# 2_bootleg-3-matrix.net
KiCad netlist of a schematic drawn in Altium Designer
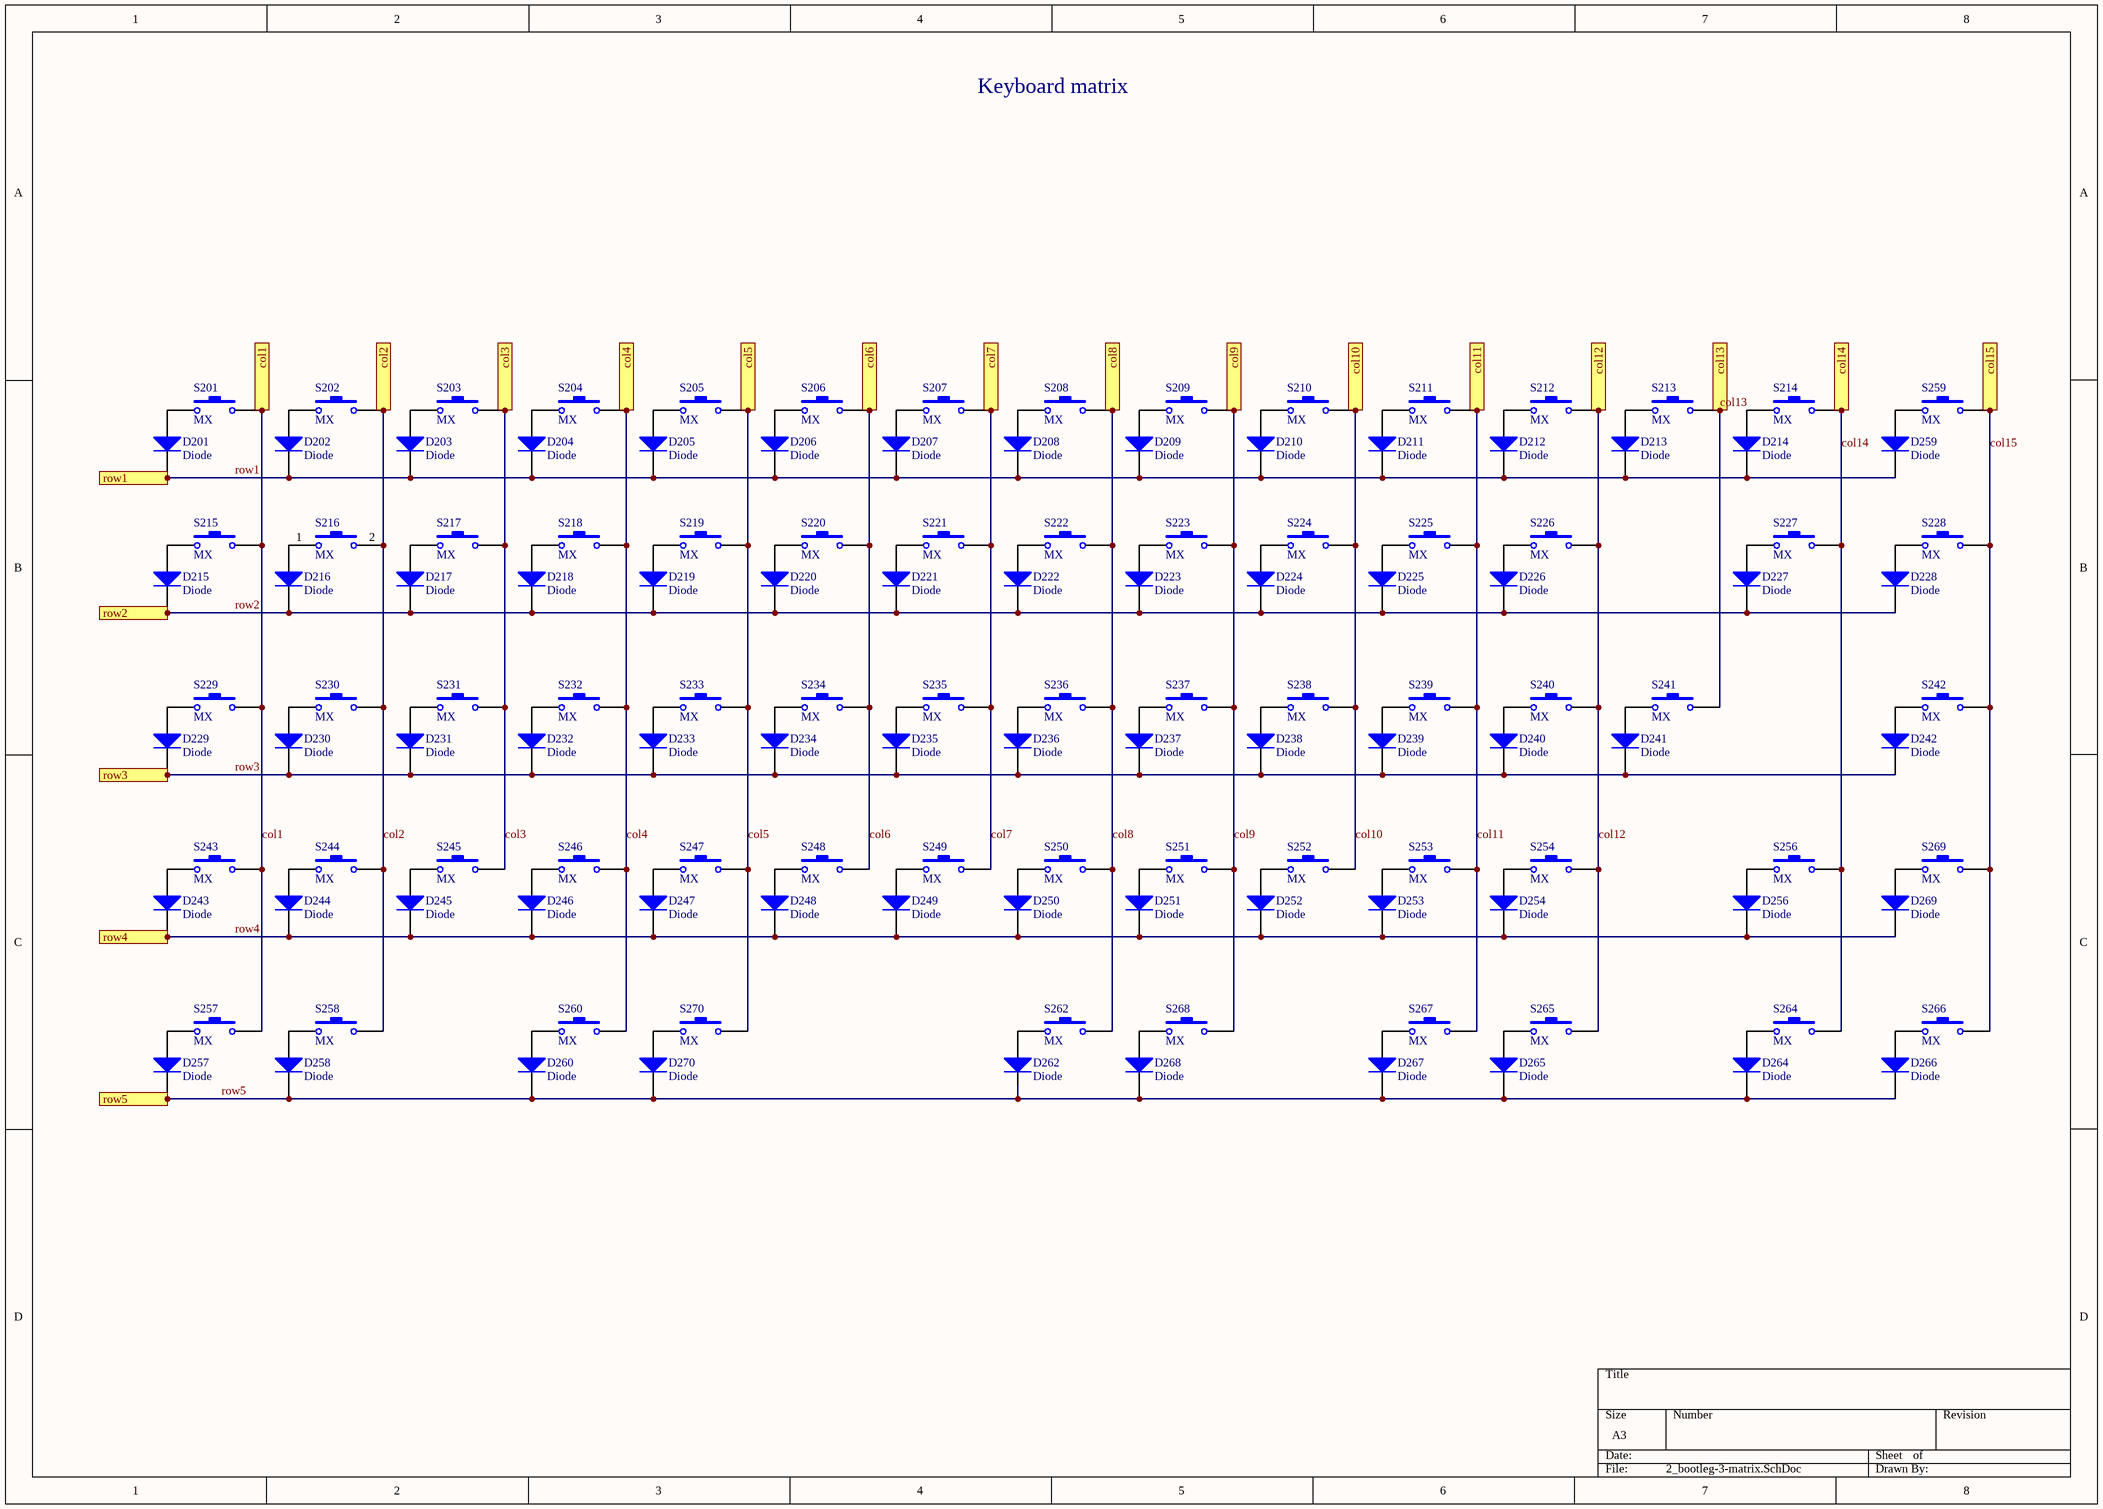
[diagram p0: 2_bootleg-3-matrix.SchDoc]

(export (version "E")
  (design (tool "Eeschema 10.0.6"))
  (components
    (comp (ref "D201")
      (value "Diode")
      (footprint "SOD-123")
      (description "Default Diode")
      (fields (field (name "MFG") "Bourns Inc.") (field (name "LCSC PART #") "C109002"))
      (libsource (lib "Miscellaneous Devices") (part "Diode"))
    )
    (comp (ref "D202")
      (value "Diode")
      (footprint "SOD-123")
      (description "Default Diode")
      (fields (field (name "MFG") "Bourns Inc.") (field (name "LCSC PART #") "C109002"))
      (libsource (lib "Miscellaneous Devices") (part "Diode"))
    )
    (comp (ref "D203")
      (value "Diode")
      (footprint "SOD-123")
      (description "Default Diode")
      (fields (field (name "MFG") "Bourns Inc.") (field (name "LCSC PART #") "C109002"))
      (libsource (lib "Miscellaneous Devices") (part "Diode"))
    )
    (comp (ref "D204")
      (value "Diode")
      (footprint "SOD-123")
      (description "Default Diode")
      (fields (field (name "MFG") "Bourns Inc.") (field (name "LCSC PART #") "C109002"))
      (libsource (lib "Miscellaneous Devices") (part "Diode"))
    )
    (comp (ref "D205")
      (value "Diode")
      (footprint "SOD-123")
      (description "Default Diode")
      (fields (field (name "MFG") "Bourns Inc.") (field (name "LCSC PART #") "C109002"))
      (libsource (lib "Miscellaneous Devices") (part "Diode"))
    )
    (comp (ref "D206")
      (value "Diode")
      (footprint "SOD-123")
      (description "Default Diode")
      (fields (field (name "MFG") "Bourns Inc.") (field (name "LCSC PART #") "C109002"))
      (libsource (lib "Miscellaneous Devices") (part "Diode"))
    )
    (comp (ref "D207")
      (value "Diode")
      (footprint "SOD-123")
      (description "Default Diode")
      (fields (field (name "MFG") "Bourns Inc.") (field (name "LCSC PART #") "C109002"))
      (libsource (lib "Miscellaneous Devices") (part "Diode"))
    )
    (comp (ref "D208")
      (value "Diode")
      (footprint "SOD-123")
      (description "Default Diode")
      (fields (field (name "MFG") "Bourns Inc.") (field (name "LCSC PART #") "C109002"))
      (libsource (lib "Miscellaneous Devices") (part "Diode"))
    )
    (comp (ref "D209")
      (value "Diode")
      (footprint "SOD-123")
      (description "Default Diode")
      (fields (field (name "MFG") "Bourns Inc.") (field (name "LCSC PART #") "C109002"))
      (libsource (lib "Miscellaneous Devices") (part "Diode"))
    )
    (comp (ref "D210")
      (value "Diode")
      (footprint "SOD-123")
      (description "Default Diode")
      (fields (field (name "MFG") "Bourns Inc.") (field (name "LCSC PART #") "C109002"))
      (libsource (lib "Miscellaneous Devices") (part "Diode"))
    )
    (comp (ref "D211")
      (value "Diode")
      (footprint "SOD-123")
      (description "Default Diode")
      (fields (field (name "MFG") "Bourns Inc.") (field (name "LCSC PART #") "C109002"))
      (libsource (lib "Miscellaneous Devices") (part "Diode"))
    )
    (comp (ref "D212")
      (value "Diode")
      (footprint "SOD-123")
      (description "Default Diode")
      (fields (field (name "MFG") "Bourns Inc.") (field (name "LCSC PART #") "C109002"))
      (libsource (lib "Miscellaneous Devices") (part "Diode"))
    )
    (comp (ref "D213")
      (value "Diode")
      (footprint "SOD-123")
      (description "Default Diode")
      (fields (field (name "MFG") "Bourns Inc.") (field (name "LCSC PART #") "C109002"))
      (libsource (lib "Miscellaneous Devices") (part "Diode"))
    )
    (comp (ref "D214")
      (value "Diode")
      (footprint "SOD-123")
      (description "Default Diode")
      (fields (field (name "MFG") "Bourns Inc.") (field (name "LCSC PART #") "C109002"))
      (libsource (lib "Miscellaneous Devices") (part "Diode"))
    )
    (comp (ref "D215")
      (value "Diode")
      (footprint "SOD-123")
      (description "Default Diode")
      (fields (field (name "MFG") "Bourns Inc.") (field (name "LCSC PART #") "C109002"))
      (libsource (lib "Miscellaneous Devices") (part "Diode"))
    )
    (comp (ref "D216")
      (value "Diode")
      (footprint "SOD-123")
      (description "Default Diode")
      (fields (field (name "MFG") "Bourns Inc.") (field (name "LCSC PART #") "C109002"))
      (libsource (lib "Miscellaneous Devices") (part "Diode"))
    )
    (comp (ref "D217")
      (value "Diode")
      (footprint "SOD-123")
      (description "Default Diode")
      (fields (field (name "MFG") "Bourns Inc.") (field (name "LCSC PART #") "C109002"))
      (libsource (lib "Miscellaneous Devices") (part "Diode"))
    )
    (comp (ref "D218")
      (value "Diode")
      (footprint "SOD-123")
      (description "Default Diode")
      (fields (field (name "MFG") "Bourns Inc.") (field (name "LCSC PART #") "C109002"))
      (libsource (lib "Miscellaneous Devices") (part "Diode"))
    )
    (comp (ref "D219")
      (value "Diode")
      (footprint "SOD-123")
      (description "Default Diode")
      (fields (field (name "MFG") "Bourns Inc.") (field (name "LCSC PART #") "C109002"))
      (libsource (lib "Miscellaneous Devices") (part "Diode"))
    )
    (comp (ref "D220")
      (value "Diode")
      (footprint "SOD-123")
      (description "Default Diode")
      (fields (field (name "MFG") "Bourns Inc.") (field (name "LCSC PART #") "C109002"))
      (libsource (lib "Miscellaneous Devices") (part "Diode"))
    )
    (comp (ref "D221")
      (value "Diode")
      (footprint "SOD-123")
      (description "Default Diode")
      (fields (field (name "MFG") "Bourns Inc.") (field (name "LCSC PART #") "C109002"))
      (libsource (lib "Miscellaneous Devices") (part "Diode"))
    )
    (comp (ref "D222")
      (value "Diode")
      (footprint "SOD-123")
      (description "Default Diode")
      (fields (field (name "MFG") "Bourns Inc.") (field (name "LCSC PART #") "C109002"))
      (libsource (lib "Miscellaneous Devices") (part "Diode"))
    )
    (comp (ref "D223")
      (value "Diode")
      (footprint "SOD-123")
      (description "Default Diode")
      (fields (field (name "MFG") "Bourns Inc.") (field (name "LCSC PART #") "C109002"))
      (libsource (lib "Miscellaneous Devices") (part "Diode"))
    )
    (comp (ref "D224")
      (value "Diode")
      (footprint "SOD-123")
      (description "Default Diode")
      (fields (field (name "MFG") "Bourns Inc.") (field (name "LCSC PART #") "C109002"))
      (libsource (lib "Miscellaneous Devices") (part "Diode"))
    )
    (comp (ref "D225")
      (value "Diode")
      (footprint "SOD-123")
      (description "Default Diode")
      (fields (field (name "MFG") "Bourns Inc.") (field (name "LCSC PART #") "C109002"))
      (libsource (lib "Miscellaneous Devices") (part "Diode"))
    )
    (comp (ref "D226")
      (value "Diode")
      (footprint "SOD-123")
      (description "Default Diode")
      (fields (field (name "MFG") "Bourns Inc.") (field (name "LCSC PART #") "C109002"))
      (libsource (lib "Miscellaneous Devices") (part "Diode"))
    )
    (comp (ref "D227")
      (value "Diode")
      (footprint "SOD-123")
      (description "Default Diode")
      (fields (field (name "MFG") "Bourns Inc.") (field (name "LCSC PART #") "C109002"))
      (libsource (lib "Miscellaneous Devices") (part "Diode"))
    )
    (comp (ref "D228")
      (value "Diode")
      (footprint "SOD-123")
      (description "Default Diode")
      (fields (field (name "MFG") "Bourns Inc.") (field (name "LCSC PART #") "C109002"))
      (libsource (lib "Miscellaneous Devices") (part "Diode"))
    )
    (comp (ref "D229")
      (value "Diode")
      (footprint "SOD-123")
      (description "Default Diode")
      (fields (field (name "MFG") "Bourns Inc.") (field (name "LCSC PART #") "C109002"))
      (libsource (lib "Miscellaneous Devices") (part "Diode"))
    )
    (comp (ref "D230")
      (value "Diode")
      (footprint "SOD-123")
      (description "Default Diode")
      (fields (field (name "MFG") "Bourns Inc.") (field (name "LCSC PART #") "C109002"))
      (libsource (lib "Miscellaneous Devices") (part "Diode"))
    )
    (comp (ref "D231")
      (value "Diode")
      (footprint "SOD-123")
      (description "Default Diode")
      (fields (field (name "MFG") "Bourns Inc.") (field (name "LCSC PART #") "C109002"))
      (libsource (lib "Miscellaneous Devices") (part "Diode"))
    )
    (comp (ref "D232")
      (value "Diode")
      (footprint "SOD-123")
      (description "Default Diode")
      (fields (field (name "MFG") "Bourns Inc.") (field (name "LCSC PART #") "C109002"))
      (libsource (lib "Miscellaneous Devices") (part "Diode"))
    )
    (comp (ref "D233")
      (value "Diode")
      (footprint "SOD-123")
      (description "Default Diode")
      (fields (field (name "MFG") "Bourns Inc.") (field (name "LCSC PART #") "C109002"))
      (libsource (lib "Miscellaneous Devices") (part "Diode"))
    )
    (comp (ref "D234")
      (value "Diode")
      (footprint "SOD-123")
      (description "Default Diode")
      (fields (field (name "MFG") "Bourns Inc.") (field (name "LCSC PART #") "C109002"))
      (libsource (lib "Miscellaneous Devices") (part "Diode"))
    )
    (comp (ref "D235")
      (value "Diode")
      (footprint "SOD-123")
      (description "Default Diode")
      (fields (field (name "MFG") "Bourns Inc.") (field (name "LCSC PART #") "C109002"))
      (libsource (lib "Miscellaneous Devices") (part "Diode"))
    )
    (comp (ref "D236")
      (value "Diode")
      (footprint "SOD-123")
      (description "Default Diode")
      (fields (field (name "MFG") "Bourns Inc.") (field (name "LCSC PART #") "C109002"))
      (libsource (lib "Miscellaneous Devices") (part "Diode"))
    )
    (comp (ref "D237")
      (value "Diode")
      (footprint "SOD-123")
      (description "Default Diode")
      (fields (field (name "MFG") "Bourns Inc.") (field (name "LCSC PART #") "C109002"))
      (libsource (lib "Miscellaneous Devices") (part "Diode"))
    )
    (comp (ref "D238")
      (value "Diode")
      (footprint "SOD-123")
      (description "Default Diode")
      (fields (field (name "MFG") "Bourns Inc.") (field (name "LCSC PART #") "C109002"))
      (libsource (lib "Miscellaneous Devices") (part "Diode"))
    )
    (comp (ref "D239")
      (value "Diode")
      (footprint "SOD-123")
      (description "Default Diode")
      (fields (field (name "MFG") "Bourns Inc.") (field (name "LCSC PART #") "C109002"))
      (libsource (lib "Miscellaneous Devices") (part "Diode"))
    )
    (comp (ref "D240")
      (value "Diode")
      (footprint "SOD-123")
      (description "Default Diode")
      (fields (field (name "MFG") "Bourns Inc.") (field (name "LCSC PART #") "C109002"))
      (libsource (lib "Miscellaneous Devices") (part "Diode"))
    )
    (comp (ref "D241")
      (value "Diode")
      (footprint "SOD-123")
      (description "Default Diode")
      (fields (field (name "MFG") "Bourns Inc.") (field (name "LCSC PART #") "C109002"))
      (libsource (lib "Miscellaneous Devices") (part "Diode"))
    )
    (comp (ref "D242")
      (value "Diode")
      (footprint "SOD-123")
      (description "Default Diode")
      (fields (field (name "MFG") "Bourns Inc.") (field (name "LCSC PART #") "C109002"))
      (libsource (lib "Miscellaneous Devices") (part "Diode"))
    )
    (comp (ref "D243")
      (value "Diode")
      (footprint "SOD-123")
      (description "Default Diode")
      (fields (field (name "MFG") "Bourns Inc.") (field (name "LCSC PART #") "C109002"))
      (libsource (lib "Miscellaneous Devices") (part "Diode"))
    )
    (comp (ref "D244")
      (value "Diode")
      (footprint "SOD-123")
      (description "Default Diode")
      (fields (field (name "MFG") "Bourns Inc.") (field (name "LCSC PART #") "C109002"))
      (libsource (lib "Miscellaneous Devices") (part "Diode"))
    )
    (comp (ref "D245")
      (value "Diode")
      (footprint "SOD-123")
      (description "Default Diode")
      (fields (field (name "MFG") "Bourns Inc.") (field (name "LCSC PART #") "C109002"))
      (libsource (lib "Miscellaneous Devices") (part "Diode"))
    )
    (comp (ref "D246")
      (value "Diode")
      (footprint "SOD-123")
      (description "Default Diode")
      (fields (field (name "MFG") "Bourns Inc.") (field (name "LCSC PART #") "C109002"))
      (libsource (lib "Miscellaneous Devices") (part "Diode"))
    )
    (comp (ref "D247")
      (value "Diode")
      (footprint "SOD-123")
      (description "Default Diode")
      (fields (field (name "MFG") "Bourns Inc.") (field (name "LCSC PART #") "C109002"))
      (libsource (lib "Miscellaneous Devices") (part "Diode"))
    )
    (comp (ref "D248")
      (value "Diode")
      (footprint "SOD-123")
      (description "Default Diode")
      (fields (field (name "MFG") "Bourns Inc.") (field (name "LCSC PART #") "C109002"))
      (libsource (lib "Miscellaneous Devices") (part "Diode"))
    )
    (comp (ref "D249")
      (value "Diode")
      (footprint "SOD-123")
      (description "Default Diode")
      (fields (field (name "MFG") "Bourns Inc.") (field (name "LCSC PART #") "C109002"))
      (libsource (lib "Miscellaneous Devices") (part "Diode"))
    )
    (comp (ref "D250")
      (value "Diode")
      (footprint "SOD-123")
      (description "Default Diode")
      (fields (field (name "MFG") "Bourns Inc.") (field (name "LCSC PART #") "C109002"))
      (libsource (lib "Miscellaneous Devices") (part "Diode"))
    )
    (comp (ref "D251")
      (value "Diode")
      (footprint "SOD-123")
      (description "Default Diode")
      (fields (field (name "MFG") "Bourns Inc.") (field (name "LCSC PART #") "C109002"))
      (libsource (lib "Miscellaneous Devices") (part "Diode"))
    )
    (comp (ref "D252")
      (value "Diode")
      (footprint "SOD-123")
      (description "Default Diode")
      (fields (field (name "MFG") "Bourns Inc.") (field (name "LCSC PART #") "C109002"))
      (libsource (lib "Miscellaneous Devices") (part "Diode"))
    )
    (comp (ref "D253")
      (value "Diode")
      (footprint "SOD-123")
      (description "Default Diode")
      (fields (field (name "MFG") "Bourns Inc.") (field (name "LCSC PART #") "C109002"))
      (libsource (lib "Miscellaneous Devices") (part "Diode"))
    )
    (comp (ref "D254")
      (value "Diode")
      (footprint "SOD-123")
      (description "Default Diode")
      (fields (field (name "MFG") "Bourns Inc.") (field (name "LCSC PART #") "C109002"))
      (libsource (lib "Miscellaneous Devices") (part "Diode"))
    )
    (comp (ref "D256")
      (value "Diode")
      (footprint "SOD-123")
      (description "Default Diode")
      (fields (field (name "MFG") "Bourns Inc.") (field (name "LCSC PART #") "C109002"))
      (libsource (lib "Miscellaneous Devices") (part "Diode"))
    )
    (comp (ref "D257")
      (value "Diode")
      (footprint "SOD-123")
      (description "Default Diode")
      (fields (field (name "MFG") "Bourns Inc.") (field (name "LCSC PART #") "C109002"))
      (libsource (lib "Miscellaneous Devices") (part "Diode"))
    )
    (comp (ref "D258")
      (value "Diode")
      (footprint "SOD-123")
      (description "Default Diode")
      (fields (field (name "MFG") "Bourns Inc.") (field (name "LCSC PART #") "C109002"))
      (libsource (lib "Miscellaneous Devices") (part "Diode"))
    )
    (comp (ref "D259")
      (value "Diode")
      (footprint "SOD-123")
      (description "Default Diode")
      (fields (field (name "MFG") "Bourns Inc.") (field (name "LCSC PART #") "C109002"))
      (libsource (lib "Miscellaneous Devices") (part "Diode"))
    )
    (comp (ref "D260")
      (value "Diode")
      (footprint "SOD-123")
      (description "Default Diode")
      (fields (field (name "MFG") "Bourns Inc.") (field (name "LCSC PART #") "C109002"))
      (libsource (lib "Miscellaneous Devices") (part "Diode"))
    )
    (comp (ref "D262")
      (value "Diode")
      (footprint "SOD-123")
      (description "Default Diode")
      (fields (field (name "MFG") "Bourns Inc.") (field (name "LCSC PART #") "C109002"))
      (libsource (lib "Miscellaneous Devices") (part "Diode"))
    )
    (comp (ref "D264")
      (value "Diode")
      (footprint "SOD-123")
      (description "Default Diode")
      (fields (field (name "MFG") "Bourns Inc.") (field (name "LCSC PART #") "C109002"))
      (libsource (lib "Miscellaneous Devices") (part "Diode"))
    )
    (comp (ref "D265")
      (value "Diode")
      (footprint "SOD-123")
      (description "Default Diode")
      (fields (field (name "MFG") "Bourns Inc.") (field (name "LCSC PART #") "C109002"))
      (libsource (lib "Miscellaneous Devices") (part "Diode"))
    )
    (comp (ref "D266")
      (value "Diode")
      (footprint "SOD-123")
      (description "Default Diode")
      (fields (field (name "MFG") "Bourns Inc.") (field (name "LCSC PART #") "C109002"))
      (libsource (lib "Miscellaneous Devices") (part "Diode"))
    )
    (comp (ref "D267")
      (value "Diode")
      (footprint "SOD-123")
      (description "Default Diode")
      (fields (field (name "MFG") "Bourns Inc.") (field (name "LCSC PART #") "C109002"))
      (libsource (lib "Miscellaneous Devices") (part "Diode"))
    )
    (comp (ref "D268")
      (value "Diode")
      (footprint "SOD-123")
      (description "Default Diode")
      (fields (field (name "MFG") "Bourns Inc.") (field (name "LCSC PART #") "C109002"))
      (libsource (lib "Miscellaneous Devices") (part "Diode"))
    )
    (comp (ref "D269")
      (value "Diode")
      (footprint "SOD-123")
      (description "Default Diode")
      (fields (field (name "MFG") "Bourns Inc.") (field (name "LCSC PART #") "C109002"))
      (libsource (lib "Miscellaneous Devices") (part "Diode"))
    )
    (comp (ref "D270")
      (value "Diode")
      (footprint "SOD-123")
      (description "Default Diode")
      (fields (field (name "MFG") "Bourns Inc.") (field (name "LCSC PART #") "C109002"))
      (libsource (lib "Miscellaneous Devices") (part "Diode"))
    )
    (comp (ref "S201")
      (value "MX")
      (footprint "SMK-switch - switched polarity")
      (description "Switch")
      (libsource (lib "Miscellaneous Devices") (part "SW-PB"))
    )
    (comp (ref "S202")
      (value "MX")
      (footprint "SMK-switch - switched polarity")
      (description "Switch")
      (libsource (lib "Miscellaneous Devices") (part "SW-PB"))
    )
    (comp (ref "S203")
      (value "MX")
      (footprint "SMK-switch - switched polarity")
      (description "Switch")
      (libsource (lib "Miscellaneous Devices") (part "SW-PB"))
    )
    (comp (ref "S204")
      (value "MX")
      (footprint "SMK-switch - switched polarity")
      (description "Switch")
      (libsource (lib "Miscellaneous Devices") (part "SW-PB"))
    )
    (comp (ref "S205")
      (value "MX")
      (footprint "SMK-switch - switched polarity")
      (description "Switch")
      (libsource (lib "Miscellaneous Devices") (part "SW-PB"))
    )
    (comp (ref "S206")
      (value "MX")
      (footprint "SMK-switch - switched polarity")
      (description "Switch")
      (libsource (lib "Miscellaneous Devices") (part "SW-PB"))
    )
    (comp (ref "S207")
      (value "MX")
      (footprint "SMK-switch - switched polarity")
      (description "Switch")
      (libsource (lib "Miscellaneous Devices") (part "SW-PB"))
    )
    (comp (ref "S208")
      (value "MX")
      (footprint "SMK-switch - switched polarity")
      (description "Switch")
      (libsource (lib "Miscellaneous Devices") (part "SW-PB"))
    )
    (comp (ref "S209")
      (value "MX")
      (footprint "SMK-switch - switched polarity")
      (description "Switch")
      (libsource (lib "Miscellaneous Devices") (part "SW-PB"))
    )
    (comp (ref "S210")
      (value "MX")
      (footprint "SMK-switch - switched polarity")
      (description "Switch")
      (libsource (lib "Miscellaneous Devices") (part "SW-PB"))
    )
    (comp (ref "S211")
      (value "MX")
      (footprint "SMK-switch - switched polarity")
      (description "Switch")
      (libsource (lib "Miscellaneous Devices") (part "SW-PB"))
    )
    (comp (ref "S212")
      (value "MX")
      (footprint "SMK-switch - switched polarity")
      (description "Switch")
      (libsource (lib "Miscellaneous Devices") (part "SW-PB"))
    )
    (comp (ref "S213")
      (value "MX")
      (footprint "SMK-switch - switched polarity")
      (description "Switch")
      (libsource (lib "Miscellaneous Devices") (part "SW-PB"))
    )
    (comp (ref "S214")
      (value "MX")
      (footprint "SMK-switch - switched polarity")
      (description "Switch")
      (libsource (lib "Miscellaneous Devices") (part "SW-PB"))
    )
    (comp (ref "S215")
      (value "MX")
      (footprint "SMK-switch - 1.5U")
      (description "TAB")
      (libsource (lib "Miscellaneous Devices") (part "SW-PB"))
    )
    (comp (ref "S216")
      (value "MX")
      (footprint "SMK-switch - switched polarity")
      (description "Switch")
      (libsource (lib "") (part "SW-PB_1"))
    )
    (comp (ref "S217")
      (value "MX")
      (footprint "SMK-switch - switched polarity")
      (description "Switch")
      (libsource (lib "Miscellaneous Devices") (part "SW-PB"))
    )
    (comp (ref "S218")
      (value "MX")
      (footprint "SMK-switch - switched polarity")
      (description "Switch")
      (libsource (lib "Miscellaneous Devices") (part "SW-PB"))
    )
    (comp (ref "S219")
      (value "MX")
      (footprint "SMK-switch - switched polarity")
      (description "Switch")
      (libsource (lib "Miscellaneous Devices") (part "SW-PB"))
    )
    (comp (ref "S220")
      (value "MX")
      (footprint "SMK-switch - switched polarity")
      (description "Switch")
      (libsource (lib "Miscellaneous Devices") (part "SW-PB"))
    )
    (comp (ref "S221")
      (value "MX")
      (footprint "SMK-switch - switched polarity")
      (description "Switch")
      (libsource (lib "Miscellaneous Devices") (part "SW-PB"))
    )
    (comp (ref "S222")
      (value "MX")
      (footprint "SMK-switch - switched polarity")
      (description "Switch")
      (libsource (lib "Miscellaneous Devices") (part "SW-PB"))
    )
    (comp (ref "S223")
      (value "MX")
      (footprint "SMK-switch - switched polarity")
      (description "Switch")
      (libsource (lib "Miscellaneous Devices") (part "SW-PB"))
    )
    (comp (ref "S224")
      (value "MX")
      (footprint "SMK-switch - switched polarity")
      (description "Switch")
      (libsource (lib "Miscellaneous Devices") (part "SW-PB"))
    )
    (comp (ref "S225")
      (value "MX")
      (footprint "SMK-switch - switched polarity")
      (description "Switch")
      (libsource (lib "Miscellaneous Devices") (part "SW-PB"))
    )
    (comp (ref "S226")
      (value "MX")
      (footprint "SMK-switch")
      (description "Switch")
      (libsource (lib "Miscellaneous Devices") (part "SW-PB"))
    )
    (comp (ref "S227")
      (value "MX")
      (footprint "SMK-switch - switched polarity")
      (description "Switch")
      (libsource (lib "Miscellaneous Devices") (part "SW-PB"))
    )
    (comp (ref "S228")
      (value "MX")
      (footprint "SMK-switch - 1.5U")
      (description "Switch")
      (libsource (lib "Miscellaneous Devices") (part "SW-PB"))
    )
    (comp (ref "S229")
      (value "MX")
      (footprint "SMK-switch - CAPS - dual")
      (description "Switch")
      (libsource (lib "Miscellaneous Devices") (part "SW-PB"))
    )
    (comp (ref "S230")
      (value "MX")
      (footprint "SMK-switch - switched polarity")
      (description "Switch")
      (libsource (lib "Miscellaneous Devices") (part "SW-PB"))
    )
    (comp (ref "S231")
      (value "MX")
      (footprint "SMK-switch - switched polarity")
      (description "Switch")
      (libsource (lib "Miscellaneous Devices") (part "SW-PB"))
    )
    (comp (ref "S232")
      (value "MX")
      (footprint "SMK-switch - switched polarity")
      (description "Switch")
      (libsource (lib "Miscellaneous Devices") (part "SW-PB"))
    )
    (comp (ref "S233")
      (value "MX")
      (footprint "SMK-switch - switched polarity")
      (description "Switch")
      (libsource (lib "Miscellaneous Devices") (part "SW-PB"))
    )
    (comp (ref "S234")
      (value "MX")
      (footprint "SMK-switch - switched polarity")
      (description "Switch")
      (libsource (lib "Miscellaneous Devices") (part "SW-PB"))
    )
    (comp (ref "S235")
      (value "MX")
      (footprint "SMK-switch - switched polarity")
      (description "Switch")
      (libsource (lib "Miscellaneous Devices") (part "SW-PB"))
    )
    (comp (ref "S236")
      (value "MX")
      (footprint "SMK-switch - switched polarity")
      (description "Switch")
      (libsource (lib "Miscellaneous Devices") (part "SW-PB"))
    )
    (comp (ref "S237")
      (value "MX")
      (footprint "SMK-switch - switched polarity")
      (description "Switch")
      (libsource (lib "Miscellaneous Devices") (part "SW-PB"))
    )
    (comp (ref "S238")
      (value "MX")
      (footprint "SMK-switch - switched polarity")
      (description "Switch")
      (libsource (lib "Miscellaneous Devices") (part "SW-PB"))
    )
    (comp (ref "S239")
      (value "MX")
      (footprint "SMK-switch")
      (description "Switch")
      (libsource (lib "Miscellaneous Devices") (part "SW-PB"))
    )
    (comp (ref "S240")
      (value "MX")
      (footprint "SMK-switch - switched polarity")
      (description "Switch")
      (libsource (lib "Miscellaneous Devices") (part "SW-PB"))
    )
    (comp (ref "S241")
      (value "MX")
      (footprint "SMK-switch")
      (description "Switch")
      (libsource (lib "Miscellaneous Devices") (part "SW-PB"))
    )
    (comp (ref "S242")
      (value "MX")
      (footprint "SMK-switch - Enter")
      (description "Switch")
      (libsource (lib "Miscellaneous Devices") (part "SW-PB"))
    )
    (comp (ref "S243")
      (value "MX")
      (footprint "SMK-switch - Left shift v2")
      (description "Switch")
      (libsource (lib "Miscellaneous Devices") (part "SW-PB"))
    )
    (comp (ref "S244")
      (value "MX")
      (footprint "SMK-switch")
      (description "Switch")
      (libsource (lib "Miscellaneous Devices") (part "SW-PB"))
    )
    (comp (ref "S245")
      (value "MX")
      (footprint "SMK-switch - switched polarity")
      (description "Switch")
      (libsource (lib "Miscellaneous Devices") (part "SW-PB"))
    )
    (comp (ref "S246")
      (value "MX")
      (footprint "SMK-switch - switched polarity")
      (description "Switch")
      (libsource (lib "Miscellaneous Devices") (part "SW-PB"))
    )
    (comp (ref "S247")
      (value "MX")
      (footprint "SMK-switch - switched polarity")
      (description "Switch")
      (libsource (lib "Miscellaneous Devices") (part "SW-PB"))
    )
    (comp (ref "S248")
      (value "MX")
      (footprint "SMK-switch - switched polarity")
      (description "Switch")
      (libsource (lib "Miscellaneous Devices") (part "SW-PB"))
    )
    (comp (ref "S249")
      (value "MX")
      (footprint "SMK-switch - switched polarity")
      (description "Switch")
      (libsource (lib "Miscellaneous Devices") (part "SW-PB"))
    )
    (comp (ref "S250")
      (value "MX")
      (footprint "SMK-switch - switched polarity")
      (description "Switch")
      (libsource (lib "Miscellaneous Devices") (part "SW-PB"))
    )
    (comp (ref "S251")
      (value "MX")
      (footprint "SMK-switch - switched polarity")
      (description "Switch")
      (libsource (lib "Miscellaneous Devices") (part "SW-PB"))
    )
    (comp (ref "S252")
      (value "MX")
      (footprint "SMK-switch - switched polarity")
      (description "Switch")
      (libsource (lib "Miscellaneous Devices") (part "SW-PB"))
    )
    (comp (ref "S253")
      (value "MX")
      (footprint "SMK-switch - switched polarity")
      (description "Switch")
      (libsource (lib "Miscellaneous Devices") (part "SW-PB"))
    )
    (comp (ref "S254")
      (value "MX")
      (footprint "SMK-switch - switched polarity")
      (description "Switch")
      (libsource (lib "Miscellaneous Devices") (part "SW-PB"))
    )
    (comp (ref "S256")
      (value "MX")
      (footprint "SMK-switch - right shift v2")
      (description "Switch")
      (libsource (lib "Miscellaneous Devices") (part "SW-PB"))
    )
    (comp (ref "S257")
      (value "MX")
      (footprint "SMK-switch - 1.5u MOD-L")
      (description "Switch")
      (libsource (lib "Miscellaneous Devices") (part "SW-PB"))
    )
    (comp (ref "S258")
      (value "MX")
      (footprint "SMK-switch - 1u MOD-L")
      (description "Switch")
      (libsource (lib "Miscellaneous Devices") (part "SW-PB"))
    )
    (comp (ref "S259")
      (value "MX")
      (footprint "SMK-switch - backspace")
      (description "Switch")
      (libsource (lib "Miscellaneous Devices") (part "SW-PB"))
    )
    (comp (ref "S260")
      (value "MX")
      (footprint "SMK-switch - 1.5u MOD-L")
      (description "Switch")
      (libsource (lib "Miscellaneous Devices") (part "SW-PB"))
    )
    (comp (ref "S262")
      (value "MX")
      (footprint "SMK-switch - Space_V3")
      (description "Switch")
      (libsource (lib "Miscellaneous Devices") (part "SW-PB"))
    )
    (comp (ref "S264")
      (value "MX")
      (footprint "SMK-switch - 1u MOD-R")
      (description "Switch")
      (libsource (lib "Miscellaneous Devices") (part "SW-PB"))
    )
    (comp (ref "S265")
      (value "MX")
      (footprint "SMK-SWITCH - 1.5U MOD-R")
      (description "Switch")
      (libsource (lib "Miscellaneous Devices") (part "SW-PB"))
    )
    (comp (ref "S266")
      (value "MX")
      (footprint "SMK-switch - 1.5u MOD-R")
      (description "Switch")
      (libsource (lib "Miscellaneous Devices") (part "SW-PB"))
    )
    (comp (ref "S267")
      (value "MX")
      (footprint "SMK-switch")
      (description "Switch")
      (libsource (lib "Miscellaneous Devices") (part "SW-PB"))
    )
    (comp (ref "S268")
      (value "MX")
      (footprint "SMK-switch - R split space_V2")
      (description "Switch")
      (libsource (lib "Miscellaneous Devices") (part "SW-PB"))
    )
    (comp (ref "S269")
      (value "MX")
      (footprint "SMK-switch")
      (description "Switch")
      (libsource (lib "Miscellaneous Devices") (part "SW-PB"))
    )
    (comp (ref "S270")
      (value "MX")
      (footprint "SMK-switch - L split space_V2")
      (description "Switch")
      (libsource (lib "Miscellaneous Devices") (part "SW-PB"))
    )
  )
  (nets
    (net (code "1") (name "/col1") (class "Default")
      (node (ref "S201") (pin "2") (pinfunction "2_2") (pintype "passive"))
      (node (ref "S215") (pin "2") (pinfunction "2_2") (pintype "passive"))
      (node (ref "S229") (pin "2") (pinfunction "2_2") (pintype "passive"))
      (node (ref "S243") (pin "2") (pinfunction "2_2") (pintype "passive"))
      (node (ref "S257") (pin "1") (pinfunction "1_1") (pintype "passive"))
    )
    (net (code "2") (name "/col2") (class "Default")
      (node (ref "S202") (pin "2") (pinfunction "2_2") (pintype "passive"))
      (node (ref "S216") (pin "2") (pinfunction "2_2") (pintype "passive"))
      (node (ref "S230") (pin "2") (pinfunction "2_2") (pintype "passive"))
      (node (ref "S244") (pin "2") (pinfunction "2_2") (pintype "passive"))
      (node (ref "S258") (pin "2") (pinfunction "2_2") (pintype "passive"))
    )
    (net (code "3") (name "/col3") (class "Default")
      (node (ref "S203") (pin "2") (pinfunction "2_2") (pintype "passive"))
      (node (ref "S217") (pin "2") (pinfunction "2_2") (pintype "passive"))
      (node (ref "S231") (pin "2") (pinfunction "2_2") (pintype "passive"))
      (node (ref "S245") (pin "2") (pinfunction "2_2") (pintype "passive"))
    )
    (net (code "4") (name "/col4") (class "Default")
      (node (ref "S204") (pin "2") (pinfunction "2_2") (pintype "passive"))
      (node (ref "S218") (pin "2") (pinfunction "2_2") (pintype "passive"))
      (node (ref "S232") (pin "2") (pinfunction "2_2") (pintype "passive"))
      (node (ref "S246") (pin "2") (pinfunction "2_2") (pintype "passive"))
      (node (ref "S260") (pin "2") (pinfunction "2_2") (pintype "passive"))
    )
    (net (code "5") (name "/col5") (class "Default")
      (node (ref "S205") (pin "2") (pinfunction "2_2") (pintype "passive"))
      (node (ref "S219") (pin "2") (pinfunction "2_2") (pintype "passive"))
      (node (ref "S233") (pin "2") (pinfunction "2_2") (pintype "passive"))
      (node (ref "S247") (pin "2") (pinfunction "2_2") (pintype "passive"))
      (node (ref "S270") (pin "2") (pinfunction "2_2") (pintype "passive"))
    )
    (net (code "6") (name "/col6") (class "Default")
      (node (ref "S206") (pin "2") (pinfunction "2_2") (pintype "passive"))
      (node (ref "S220") (pin "2") (pinfunction "2_2") (pintype "passive"))
      (node (ref "S234") (pin "2") (pinfunction "2_2") (pintype "passive"))
      (node (ref "S248") (pin "2") (pinfunction "2_2") (pintype "passive"))
    )
    (net (code "7") (name "/col7") (class "Default")
      (node (ref "S207") (pin "2") (pinfunction "2_2") (pintype "passive"))
      (node (ref "S221") (pin "2") (pinfunction "2_2") (pintype "passive"))
      (node (ref "S235") (pin "2") (pinfunction "2_2") (pintype "passive"))
      (node (ref "S249") (pin "2") (pinfunction "2_2") (pintype "passive"))
    )
    (net (code "8") (name "/col8") (class "Default")
      (node (ref "S208") (pin "2") (pinfunction "2_2") (pintype "passive"))
      (node (ref "S222") (pin "2") (pinfunction "2_2") (pintype "passive"))
      (node (ref "S236") (pin "2") (pinfunction "2_2") (pintype "passive"))
      (node (ref "S250") (pin "2") (pinfunction "2_2") (pintype "passive"))
      (node (ref "S262") (pin "1") (pinfunction "1_1") (pintype "passive"))
    )
    (net (code "9") (name "/col9") (class "Default")
      (node (ref "S209") (pin "2") (pinfunction "2_2") (pintype "passive"))
      (node (ref "S223") (pin "2") (pinfunction "2_2") (pintype "passive"))
      (node (ref "S237") (pin "2") (pinfunction "2_2") (pintype "passive"))
      (node (ref "S251") (pin "2") (pinfunction "2_2") (pintype "passive"))
      (node (ref "S268") (pin "2") (pinfunction "2_2") (pintype "passive"))
    )
    (net (code "10") (name "/col10") (class "Default")
      (node (ref "S210") (pin "2") (pinfunction "2_2") (pintype "passive"))
      (node (ref "S224") (pin "2") (pinfunction "2_2") (pintype "passive"))
      (node (ref "S238") (pin "2") (pinfunction "2_2") (pintype "passive"))
      (node (ref "S252") (pin "2") (pinfunction "2_2") (pintype "passive"))
    )
    (net (code "11") (name "/col11") (class "Default")
      (node (ref "S211") (pin "2") (pinfunction "2_2") (pintype "passive"))
      (node (ref "S225") (pin "2") (pinfunction "2_2") (pintype "passive"))
      (node (ref "S239") (pin "2") (pinfunction "2_2") (pintype "passive"))
      (node (ref "S253") (pin "2") (pinfunction "2_2") (pintype "passive"))
      (node (ref "S267") (pin "2") (pinfunction "2_2") (pintype "passive"))
    )
    (net (code "12") (name "/col12") (class "Default")
      (node (ref "S212") (pin "2") (pinfunction "2_2") (pintype "passive"))
      (node (ref "S226") (pin "2") (pinfunction "2_2") (pintype "passive"))
      (node (ref "S240") (pin "2") (pinfunction "2_2") (pintype "passive"))
      (node (ref "S254") (pin "2") (pinfunction "2_2") (pintype "passive"))
      (node (ref "S265") (pin "1") (pinfunction "1_1") (pintype "passive"))
    )
    (net (code "13") (name "/col13") (class "Default")
      (node (ref "S213") (pin "2") (pinfunction "2_2") (pintype "passive"))
      (node (ref "S241") (pin "2") (pinfunction "2_2") (pintype "passive"))
    )
    (net (code "14") (name "/col14") (class "Default")
      (node (ref "S214") (pin "2") (pinfunction "2_2") (pintype "passive"))
      (node (ref "S227") (pin "2") (pinfunction "2_2") (pintype "passive"))
      (node (ref "S256") (pin "2") (pinfunction "2_2") (pintype "passive"))
      (node (ref "S264") (pin "2") (pinfunction "2_2") (pintype "passive"))
    )
    (net (code "15") (name "/col15") (class "Default")
      (node (ref "S228") (pin "2") (pinfunction "2_2") (pintype "passive"))
      (node (ref "S242") (pin "1") (pinfunction "1_1") (pintype "passive"))
      (node (ref "S259") (pin "2") (pinfunction "2_2") (pintype "passive"))
      (node (ref "S266") (pin "2") (pinfunction "2_2") (pintype "passive"))
      (node (ref "S269") (pin "2") (pinfunction "2_2") (pintype "passive"))
    )
    (net (code "16") (name "/row1") (class "Default")
      (node (ref "D201") (pin "2") (pinfunction "K_2") (pintype "passive"))
      (node (ref "D202") (pin "2") (pinfunction "K_2") (pintype "passive"))
      (node (ref "D203") (pin "2") (pinfunction "K_2") (pintype "passive"))
      (node (ref "D204") (pin "2") (pinfunction "K_2") (pintype "passive"))
      (node (ref "D205") (pin "2") (pinfunction "K_2") (pintype "passive"))
      (node (ref "D206") (pin "2") (pinfunction "K_2") (pintype "passive"))
      (node (ref "D207") (pin "2") (pinfunction "K_2") (pintype "passive"))
      (node (ref "D208") (pin "2") (pinfunction "K_2") (pintype "passive"))
      (node (ref "D209") (pin "2") (pinfunction "K_2") (pintype "passive"))
      (node (ref "D210") (pin "2") (pinfunction "K_2") (pintype "passive"))
      (node (ref "D211") (pin "2") (pinfunction "K_2") (pintype "passive"))
      (node (ref "D212") (pin "2") (pinfunction "K_2") (pintype "passive"))
      (node (ref "D213") (pin "2") (pinfunction "K_2") (pintype "passive"))
      (node (ref "D214") (pin "2") (pinfunction "K_2") (pintype "passive"))
      (node (ref "D259") (pin "2") (pinfunction "K_2") (pintype "passive"))
    )
    (net (code "17") (name "/row2") (class "Default")
      (node (ref "D215") (pin "2") (pinfunction "K_2") (pintype "passive"))
      (node (ref "D216") (pin "2") (pinfunction "K_2") (pintype "passive"))
      (node (ref "D217") (pin "2") (pinfunction "K_2") (pintype "passive"))
      (node (ref "D218") (pin "2") (pinfunction "K_2") (pintype "passive"))
      (node (ref "D219") (pin "2") (pinfunction "K_2") (pintype "passive"))
      (node (ref "D220") (pin "2") (pinfunction "K_2") (pintype "passive"))
      (node (ref "D221") (pin "2") (pinfunction "K_2") (pintype "passive"))
      (node (ref "D222") (pin "2") (pinfunction "K_2") (pintype "passive"))
      (node (ref "D223") (pin "2") (pinfunction "K_2") (pintype "passive"))
      (node (ref "D224") (pin "2") (pinfunction "K_2") (pintype "passive"))
      (node (ref "D225") (pin "2") (pinfunction "K_2") (pintype "passive"))
      (node (ref "D226") (pin "2") (pinfunction "K_2") (pintype "passive"))
      (node (ref "D227") (pin "2") (pinfunction "K_2") (pintype "passive"))
      (node (ref "D228") (pin "2") (pinfunction "K_2") (pintype "passive"))
    )
    (net (code "18") (name "/row3") (class "Default")
      (node (ref "D229") (pin "2") (pinfunction "K_2") (pintype "passive"))
      (node (ref "D230") (pin "2") (pinfunction "K_2") (pintype "passive"))
      (node (ref "D231") (pin "2") (pinfunction "K_2") (pintype "passive"))
      (node (ref "D232") (pin "2") (pinfunction "K_2") (pintype "passive"))
      (node (ref "D233") (pin "2") (pinfunction "K_2") (pintype "passive"))
      (node (ref "D234") (pin "2") (pinfunction "K_2") (pintype "passive"))
      (node (ref "D235") (pin "2") (pinfunction "K_2") (pintype "passive"))
      (node (ref "D236") (pin "2") (pinfunction "K_2") (pintype "passive"))
      (node (ref "D237") (pin "2") (pinfunction "K_2") (pintype "passive"))
      (node (ref "D238") (pin "2") (pinfunction "K_2") (pintype "passive"))
      (node (ref "D239") (pin "2") (pinfunction "K_2") (pintype "passive"))
      (node (ref "D240") (pin "2") (pinfunction "K_2") (pintype "passive"))
      (node (ref "D241") (pin "2") (pinfunction "K_2") (pintype "passive"))
      (node (ref "D242") (pin "2") (pinfunction "K_2") (pintype "passive"))
    )
    (net (code "19") (name "/row4") (class "Default")
      (node (ref "D243") (pin "2") (pinfunction "K_2") (pintype "passive"))
      (node (ref "D244") (pin "2") (pinfunction "K_2") (pintype "passive"))
      (node (ref "D245") (pin "2") (pinfunction "K_2") (pintype "passive"))
      (node (ref "D246") (pin "2") (pinfunction "K_2") (pintype "passive"))
      (node (ref "D247") (pin "2") (pinfunction "K_2") (pintype "passive"))
      (node (ref "D248") (pin "2") (pinfunction "K_2") (pintype "passive"))
      (node (ref "D249") (pin "2") (pinfunction "K_2") (pintype "passive"))
      (node (ref "D250") (pin "2") (pinfunction "K_2") (pintype "passive"))
      (node (ref "D251") (pin "2") (pinfunction "K_2") (pintype "passive"))
      (node (ref "D252") (pin "2") (pinfunction "K_2") (pintype "passive"))
      (node (ref "D253") (pin "2") (pinfunction "K_2") (pintype "passive"))
      (node (ref "D254") (pin "2") (pinfunction "K_2") (pintype "passive"))
      (node (ref "D256") (pin "2") (pinfunction "K_2") (pintype "passive"))
      (node (ref "D269") (pin "2") (pinfunction "K_2") (pintype "passive"))
    )
    (net (code "20") (name "/row5") (class "Default")
      (node (ref "D257") (pin "2") (pinfunction "K_2") (pintype "passive"))
      (node (ref "D258") (pin "2") (pinfunction "K_2") (pintype "passive"))
      (node (ref "D260") (pin "2") (pinfunction "K_2") (pintype "passive"))
      (node (ref "D262") (pin "2") (pinfunction "K_2") (pintype "passive"))
      (node (ref "D264") (pin "2") (pinfunction "K_2") (pintype "passive"))
      (node (ref "D265") (pin "2") (pinfunction "K_2") (pintype "passive"))
      (node (ref "D266") (pin "2") (pinfunction "K_2") (pintype "passive"))
      (node (ref "D267") (pin "2") (pinfunction "K_2") (pintype "passive"))
      (node (ref "D268") (pin "2") (pinfunction "K_2") (pintype "passive"))
      (node (ref "D270") (pin "2") (pinfunction "K_2") (pintype "passive"))
    )
    (net (code "21") (name "Net-(D201-A)") (class "Default")
      (node (ref "D201") (pin "1") (pinfunction "A_1") (pintype "passive"))
      (node (ref "S201") (pin "1") (pinfunction "1_1") (pintype "passive"))
    )
    (net (code "22") (name "Net-(D202-A)") (class "Default")
      (node (ref "D202") (pin "1") (pinfunction "A_1") (pintype "passive"))
      (node (ref "S202") (pin "1") (pinfunction "1_1") (pintype "passive"))
    )
    (net (code "23") (name "Net-(D203-A)") (class "Default")
      (node (ref "D203") (pin "1") (pinfunction "A_1") (pintype "passive"))
      (node (ref "S203") (pin "1") (pinfunction "1_1") (pintype "passive"))
    )
    (net (code "24") (name "Net-(D204-A)") (class "Default")
      (node (ref "D204") (pin "1") (pinfunction "A_1") (pintype "passive"))
      (node (ref "S204") (pin "1") (pinfunction "1_1") (pintype "passive"))
    )
    (net (code "25") (name "Net-(D205-A)") (class "Default")
      (node (ref "D205") (pin "1") (pinfunction "A_1") (pintype "passive"))
      (node (ref "S205") (pin "1") (pinfunction "1_1") (pintype "passive"))
    )
    (net (code "26") (name "Net-(D206-A)") (class "Default")
      (node (ref "D206") (pin "1") (pinfunction "A_1") (pintype "passive"))
      (node (ref "S206") (pin "1") (pinfunction "1_1") (pintype "passive"))
    )
    (net (code "27") (name "Net-(D207-A)") (class "Default")
      (node (ref "D207") (pin "1") (pinfunction "A_1") (pintype "passive"))
      (node (ref "S207") (pin "1") (pinfunction "1_1") (pintype "passive"))
    )
    (net (code "28") (name "Net-(D208-A)") (class "Default")
      (node (ref "D208") (pin "1") (pinfunction "A_1") (pintype "passive"))
      (node (ref "S208") (pin "1") (pinfunction "1_1") (pintype "passive"))
    )
    (net (code "29") (name "Net-(D209-A)") (class "Default")
      (node (ref "D209") (pin "1") (pinfunction "A_1") (pintype "passive"))
      (node (ref "S209") (pin "1") (pinfunction "1_1") (pintype "passive"))
    )
    (net (code "30") (name "Net-(D210-A)") (class "Default")
      (node (ref "D210") (pin "1") (pinfunction "A_1") (pintype "passive"))
      (node (ref "S210") (pin "1") (pinfunction "1_1") (pintype "passive"))
    )
    (net (code "31") (name "Net-(D211-A)") (class "Default")
      (node (ref "D211") (pin "1") (pinfunction "A_1") (pintype "passive"))
      (node (ref "S211") (pin "1") (pinfunction "1_1") (pintype "passive"))
    )
    (net (code "32") (name "Net-(D212-A)") (class "Default")
      (node (ref "D212") (pin "1") (pinfunction "A_1") (pintype "passive"))
      (node (ref "S212") (pin "1") (pinfunction "1_1") (pintype "passive"))
    )
    (net (code "33") (name "Net-(D213-A)") (class "Default")
      (node (ref "D213") (pin "1") (pinfunction "A_1") (pintype "passive"))
      (node (ref "S213") (pin "1") (pinfunction "1_1") (pintype "passive"))
    )
    (net (code "34") (name "Net-(D214-A)") (class "Default")
      (node (ref "D214") (pin "1") (pinfunction "A_1") (pintype "passive"))
      (node (ref "S214") (pin "1") (pinfunction "1_1") (pintype "passive"))
    )
    (net (code "35") (name "Net-(D215-A)") (class "Default")
      (node (ref "D215") (pin "1") (pinfunction "A_1") (pintype "passive"))
      (node (ref "S215") (pin "1") (pinfunction "1_1") (pintype "passive"))
    )
    (net (code "36") (name "Net-(D216-A)") (class "Default")
      (node (ref "D216") (pin "1") (pinfunction "A_1") (pintype "passive"))
      (node (ref "S216") (pin "1") (pinfunction "1_1") (pintype "passive"))
    )
    (net (code "37") (name "Net-(D217-A)") (class "Default")
      (node (ref "D217") (pin "1") (pinfunction "A_1") (pintype "passive"))
      (node (ref "S217") (pin "1") (pinfunction "1_1") (pintype "passive"))
    )
    (net (code "38") (name "Net-(D218-A)") (class "Default")
      (node (ref "D218") (pin "1") (pinfunction "A_1") (pintype "passive"))
      (node (ref "S218") (pin "1") (pinfunction "1_1") (pintype "passive"))
    )
    (net (code "39") (name "Net-(D219-A)") (class "Default")
      (node (ref "D219") (pin "1") (pinfunction "A_1") (pintype "passive"))
      (node (ref "S219") (pin "1") (pinfunction "1_1") (pintype "passive"))
    )
    (net (code "40") (name "Net-(D220-A)") (class "Default")
      (node (ref "D220") (pin "1") (pinfunction "A_1") (pintype "passive"))
      (node (ref "S220") (pin "1") (pinfunction "1_1") (pintype "passive"))
    )
    (net (code "41") (name "Net-(D221-A)") (class "Default")
      (node (ref "D221") (pin "1") (pinfunction "A_1") (pintype "passive"))
      (node (ref "S221") (pin "1") (pinfunction "1_1") (pintype "passive"))
    )
    (net (code "42") (name "Net-(D222-A)") (class "Default")
      (node (ref "D222") (pin "1") (pinfunction "A_1") (pintype "passive"))
      (node (ref "S222") (pin "1") (pinfunction "1_1") (pintype "passive"))
    )
    (net (code "43") (name "Net-(D223-A)") (class "Default")
      (node (ref "D223") (pin "1") (pinfunction "A_1") (pintype "passive"))
      (node (ref "S223") (pin "1") (pinfunction "1_1") (pintype "passive"))
    )
    (net (code "44") (name "Net-(D224-A)") (class "Default")
      (node (ref "D224") (pin "1") (pinfunction "A_1") (pintype "passive"))
      (node (ref "S224") (pin "1") (pinfunction "1_1") (pintype "passive"))
    )
    (net (code "45") (name "Net-(D225-A)") (class "Default")
      (node (ref "D225") (pin "1") (pinfunction "A_1") (pintype "passive"))
      (node (ref "S225") (pin "1") (pinfunction "1_1") (pintype "passive"))
    )
    (net (code "46") (name "Net-(D226-A)") (class "Default")
      (node (ref "D226") (pin "1") (pinfunction "A_1") (pintype "passive"))
      (node (ref "S226") (pin "1") (pinfunction "1_1") (pintype "passive"))
    )
    (net (code "47") (name "Net-(D227-A)") (class "Default")
      (node (ref "D227") (pin "1") (pinfunction "A_1") (pintype "passive"))
      (node (ref "S227") (pin "1") (pinfunction "1_1") (pintype "passive"))
    )
    (net (code "48") (name "Net-(D228-A)") (class "Default")
      (node (ref "D228") (pin "1") (pinfunction "A_1") (pintype "passive"))
      (node (ref "S228") (pin "1") (pinfunction "1_1") (pintype "passive"))
    )
    (net (code "49") (name "Net-(D229-A)") (class "Default")
      (node (ref "D229") (pin "1") (pinfunction "A_1") (pintype "passive"))
      (node (ref "S229") (pin "1") (pinfunction "1_1") (pintype "passive"))
    )
    (net (code "50") (name "Net-(D230-A)") (class "Default")
      (node (ref "D230") (pin "1") (pinfunction "A_1") (pintype "passive"))
      (node (ref "S230") (pin "1") (pinfunction "1_1") (pintype "passive"))
    )
    (net (code "51") (name "Net-(D231-A)") (class "Default")
      (node (ref "D231") (pin "1") (pinfunction "A_1") (pintype "passive"))
      (node (ref "S231") (pin "1") (pinfunction "1_1") (pintype "passive"))
    )
    (net (code "52") (name "Net-(D232-A)") (class "Default")
      (node (ref "D232") (pin "1") (pinfunction "A_1") (pintype "passive"))
      (node (ref "S232") (pin "1") (pinfunction "1_1") (pintype "passive"))
    )
    (net (code "53") (name "Net-(D233-A)") (class "Default")
      (node (ref "D233") (pin "1") (pinfunction "A_1") (pintype "passive"))
      (node (ref "S233") (pin "1") (pinfunction "1_1") (pintype "passive"))
    )
    (net (code "54") (name "Net-(D234-A)") (class "Default")
      (node (ref "D234") (pin "1") (pinfunction "A_1") (pintype "passive"))
      (node (ref "S234") (pin "1") (pinfunction "1_1") (pintype "passive"))
    )
    (net (code "55") (name "Net-(D235-A)") (class "Default")
      (node (ref "D235") (pin "1") (pinfunction "A_1") (pintype "passive"))
      (node (ref "S235") (pin "1") (pinfunction "1_1") (pintype "passive"))
    )
    (net (code "56") (name "Net-(D236-A)") (class "Default")
      (node (ref "D236") (pin "1") (pinfunction "A_1") (pintype "passive"))
      (node (ref "S236") (pin "1") (pinfunction "1_1") (pintype "passive"))
    )
    (net (code "57") (name "Net-(D237-A)") (class "Default")
      (node (ref "D237") (pin "1") (pinfunction "A_1") (pintype "passive"))
      (node (ref "S237") (pin "1") (pinfunction "1_1") (pintype "passive"))
    )
    (net (code "58") (name "Net-(D238-A)") (class "Default")
      (node (ref "D238") (pin "1") (pinfunction "A_1") (pintype "passive"))
      (node (ref "S238") (pin "1") (pinfunction "1_1") (pintype "passive"))
    )
    (net (code "59") (name "Net-(D239-A)") (class "Default")
      (node (ref "D239") (pin "1") (pinfunction "A_1") (pintype "passive"))
      (node (ref "S239") (pin "1") (pinfunction "1_1") (pintype "passive"))
    )
    (net (code "60") (name "Net-(D240-A)") (class "Default")
      (node (ref "D240") (pin "1") (pinfunction "A_1") (pintype "passive"))
      (node (ref "S240") (pin "1") (pinfunction "1_1") (pintype "passive"))
    )
    (net (code "61") (name "Net-(D241-A)") (class "Default")
      (node (ref "D241") (pin "1") (pinfunction "A_1") (pintype "passive"))
      (node (ref "S241") (pin "1") (pinfunction "1_1") (pintype "passive"))
    )
    (net (code "62") (name "Net-(D242-A)") (class "Default")
      (node (ref "D242") (pin "1") (pinfunction "A_1") (pintype "passive"))
      (node (ref "S242") (pin "2") (pinfunction "2_2") (pintype "passive"))
    )
    (net (code "63") (name "Net-(D243-A)") (class "Default")
      (node (ref "D243") (pin "1") (pinfunction "A_1") (pintype "passive"))
      (node (ref "S243") (pin "1") (pinfunction "1_1") (pintype "passive"))
    )
    (net (code "64") (name "Net-(D244-A)") (class "Default")
      (node (ref "D244") (pin "1") (pinfunction "A_1") (pintype "passive"))
      (node (ref "S244") (pin "1") (pinfunction "1_1") (pintype "passive"))
    )
    (net (code "65") (name "Net-(D245-A)") (class "Default")
      (node (ref "D245") (pin "1") (pinfunction "A_1") (pintype "passive"))
      (node (ref "S245") (pin "1") (pinfunction "1_1") (pintype "passive"))
    )
    (net (code "66") (name "Net-(D246-A)") (class "Default")
      (node (ref "D246") (pin "1") (pinfunction "A_1") (pintype "passive"))
      (node (ref "S246") (pin "1") (pinfunction "1_1") (pintype "passive"))
    )
    (net (code "67") (name "Net-(D247-A)") (class "Default")
      (node (ref "D247") (pin "1") (pinfunction "A_1") (pintype "passive"))
      (node (ref "S247") (pin "1") (pinfunction "1_1") (pintype "passive"))
    )
    (net (code "68") (name "Net-(D248-A)") (class "Default")
      (node (ref "D248") (pin "1") (pinfunction "A_1") (pintype "passive"))
      (node (ref "S248") (pin "1") (pinfunction "1_1") (pintype "passive"))
    )
    (net (code "69") (name "Net-(D249-A)") (class "Default")
      (node (ref "D249") (pin "1") (pinfunction "A_1") (pintype "passive"))
      (node (ref "S249") (pin "1") (pinfunction "1_1") (pintype "passive"))
    )
    (net (code "70") (name "Net-(D250-A)") (class "Default")
      (node (ref "D250") (pin "1") (pinfunction "A_1") (pintype "passive"))
      (node (ref "S250") (pin "1") (pinfunction "1_1") (pintype "passive"))
    )
    (net (code "71") (name "Net-(D251-A)") (class "Default")
      (node (ref "D251") (pin "1") (pinfunction "A_1") (pintype "passive"))
      (node (ref "S251") (pin "1") (pinfunction "1_1") (pintype "passive"))
    )
    (net (code "72") (name "Net-(D252-A)") (class "Default")
      (node (ref "D252") (pin "1") (pinfunction "A_1") (pintype "passive"))
      (node (ref "S252") (pin "1") (pinfunction "1_1") (pintype "passive"))
    )
    (net (code "73") (name "Net-(D253-A)") (class "Default")
      (node (ref "D253") (pin "1") (pinfunction "A_1") (pintype "passive"))
      (node (ref "S253") (pin "1") (pinfunction "1_1") (pintype "passive"))
    )
    (net (code "74") (name "Net-(D254-A)") (class "Default")
      (node (ref "D254") (pin "1") (pinfunction "A_1") (pintype "passive"))
      (node (ref "S254") (pin "1") (pinfunction "1_1") (pintype "passive"))
    )
    (net (code "75") (name "Net-(D256-A)") (class "Default")
      (node (ref "D256") (pin "1") (pinfunction "A_1") (pintype "passive"))
      (node (ref "S256") (pin "1") (pinfunction "1_1") (pintype "passive"))
    )
    (net (code "76") (name "Net-(D257-A)") (class "Default")
      (node (ref "D257") (pin "1") (pinfunction "A_1") (pintype "passive"))
      (node (ref "S257") (pin "2") (pinfunction "2_2") (pintype "passive"))
    )
    (net (code "77") (name "Net-(D258-A)") (class "Default")
      (node (ref "D258") (pin "1") (pinfunction "A_1") (pintype "passive"))
      (node (ref "S258") (pin "1") (pinfunction "1_1") (pintype "passive"))
    )
    (net (code "78") (name "Net-(D259-A)") (class "Default")
      (node (ref "D259") (pin "1") (pinfunction "A_1") (pintype "passive"))
      (node (ref "S259") (pin "1") (pinfunction "1_1") (pintype "passive"))
    )
    (net (code "79") (name "Net-(D260-A)") (class "Default")
      (node (ref "D260") (pin "1") (pinfunction "A_1") (pintype "passive"))
      (node (ref "S260") (pin "1") (pinfunction "1_1") (pintype "passive"))
    )
    (net (code "80") (name "Net-(D262-A)") (class "Default")
      (node (ref "D262") (pin "1") (pinfunction "A_1") (pintype "passive"))
      (node (ref "S262") (pin "2") (pinfunction "2_2") (pintype "passive"))
    )
    (net (code "81") (name "Net-(D264-A)") (class "Default")
      (node (ref "D264") (pin "1") (pinfunction "A_1") (pintype "passive"))
      (node (ref "S264") (pin "1") (pinfunction "1_1") (pintype "passive"))
    )
    (net (code "82") (name "Net-(D265-A)") (class "Default")
      (node (ref "D265") (pin "1") (pinfunction "A_1") (pintype "passive"))
      (node (ref "S265") (pin "2") (pinfunction "2_2") (pintype "passive"))
    )
    (net (code "83") (name "Net-(D266-A)") (class "Default")
      (node (ref "D266") (pin "1") (pinfunction "A_1") (pintype "passive"))
      (node (ref "S266") (pin "1") (pinfunction "1_1") (pintype "passive"))
    )
    (net (code "84") (name "Net-(D267-A)") (class "Default")
      (node (ref "D267") (pin "1") (pinfunction "A_1") (pintype "passive"))
      (node (ref "S267") (pin "1") (pinfunction "1_1") (pintype "passive"))
    )
    (net (code "85") (name "Net-(D268-A)") (class "Default")
      (node (ref "D268") (pin "1") (pinfunction "A_1") (pintype "passive"))
      (node (ref "S268") (pin "1") (pinfunction "1_1") (pintype "passive"))
    )
    (net (code "86") (name "Net-(D269-A)") (class "Default")
      (node (ref "D269") (pin "1") (pinfunction "A_1") (pintype "passive"))
      (node (ref "S269") (pin "1") (pinfunction "1_1") (pintype "passive"))
    )
    (net (code "87") (name "Net-(D270-A)") (class "Default")
      (node (ref "D270") (pin "1") (pinfunction "A_1") (pintype "passive"))
      (node (ref "S270") (pin "1") (pinfunction "1_1") (pintype "passive"))
    )
  )
)
